# Ex_Controller_ExPwr.net
KiCad netlist of a schematic drawn in EAGLE
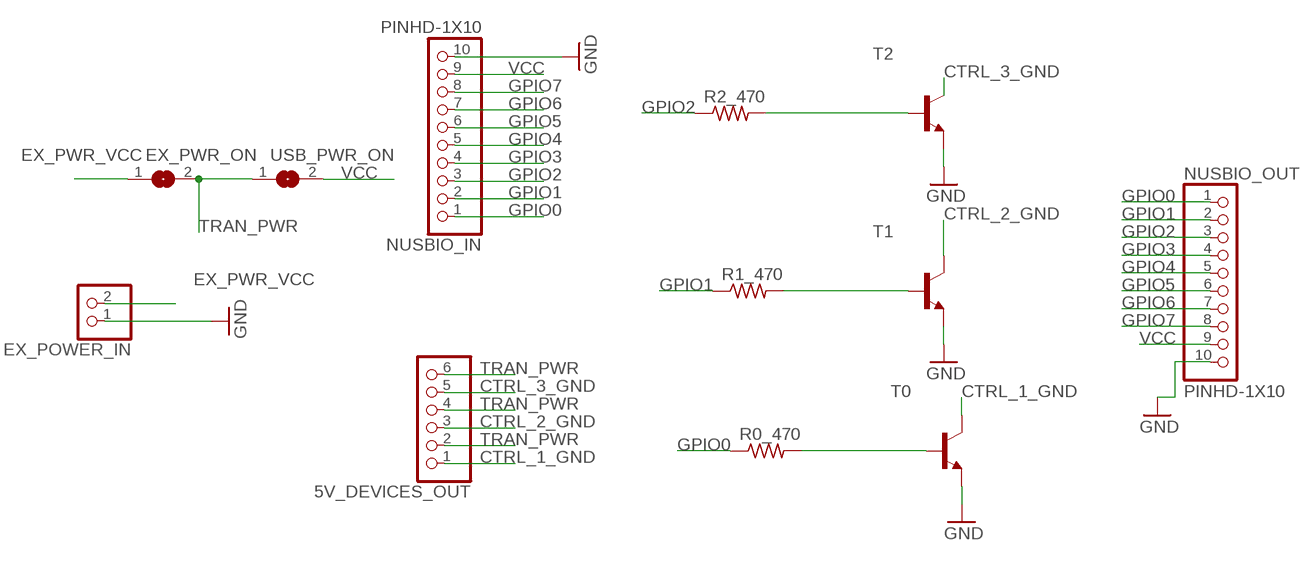
[diagram p0: schematic, sheet 1]

(export (version "E")
  (design (tool "Eeschema 10.0.6"))
  (components
    (comp (ref "5V_DEVICES_OUT")
      (value "PINHD-1X6")
      (footprint "eagle-import:1X06")
      (libsource (lib "eagle-import") (part "PINHD-1X6"))
    )
    (comp (ref "EX_POWER_IN")
      (value "PINHD-1X2")
      (footprint "eagle-import:1X02")
      (libsource (lib "eagle-import") (part "PINHD-1X2"))
    )
    (comp (ref "EX_PWR_ON")
      (value "SOLDERJUMPERREFLOW")
      (footprint "eagle-import:SOLDERJUMPER_REFLOW")
      (libsource (lib "eagle-import") (part "SOLDERJUMPERREFLOW"))
    )
    (comp (ref "NUSBIO_IN")
      (value "PINHD-1X10")
      (footprint "eagle-import:1X10-BIG")
      (libsource (lib "eagle-import") (part "PINHD-1X10"))
    )
    (comp (ref "NUSBIO_OUT")
      (value "PINHD-1X10")
      (footprint "eagle-import:1X10-BIG")
      (libsource (lib "eagle-import") (part "PINHD-1X10"))
    )
    (comp (ref "R0_470")
      (value "R-US_R0805")
      (footprint "eagle-import:R0805")
      (libsource (lib "eagle-import") (part "R-US_R0805"))
    )
    (comp (ref "R1_470")
      (value "R-US_R0805")
      (footprint "eagle-import:R0805")
      (libsource (lib "eagle-import") (part "R-US_R0805"))
    )
    (comp (ref "R2_470")
      (value "R-US_R0805")
      (footprint "eagle-import:R0805")
      (libsource (lib "eagle-import") (part "R-US_R0805"))
    )
    (comp (ref "T0")
      (value "MMBT3904LT1-NPN-SOT23-BEC")
      (footprint "eagle-import:SOT23-BEC")
      (libsource (lib "eagle-import") (part "-NPN-SOT23-BECMMBT3904LT1"))
    )
    (comp (ref "T1")
      (value "MMBT3904LT1-NPN-SOT23-BEC")
      (footprint "eagle-import:SOT23-BEC")
      (libsource (lib "eagle-import") (part "-NPN-SOT23-BECMMBT3904LT1"))
    )
    (comp (ref "T2")
      (value "MMBT3904LT1-NPN-SOT23-BEC")
      (footprint "eagle-import:SOT23-BEC")
      (libsource (lib "eagle-import") (part "-NPN-SOT23-BECMMBT3904LT1"))
    )
    (comp (ref "USB_PWR_ON")
      (value "SOLDERJUMPERREFLOW")
      (footprint "eagle-import:SOLDERJUMPER_REFLOW")
      (libsource (lib "eagle-import") (part "SOLDERJUMPERREFLOW"))
    )
  )
  (nets
    (net (code "1") (name "/CTRL_1_GND") (class "Default")
      (node (ref "5V_DEVICES_OUT") (pin "1") (pinfunction "1_1") (pintype "passive"))
      (node (ref "T0") (pin "C") (pinfunction "C_C") (pintype "passive"))
    )
    (net (code "2") (name "/CTRL_2_GND") (class "Default")
      (node (ref "5V_DEVICES_OUT") (pin "3") (pinfunction "3_3") (pintype "passive"))
      (node (ref "T1") (pin "C") (pinfunction "C_C") (pintype "passive"))
    )
    (net (code "3") (name "/CTRL_3_GND") (class "Default")
      (node (ref "5V_DEVICES_OUT") (pin "5") (pinfunction "5_5") (pintype "passive"))
      (node (ref "T2") (pin "C") (pinfunction "C_C") (pintype "passive"))
    )
    (net (code "4") (name "/EX_PWR_VCC") (class "Default")
      (node (ref "EX_POWER_IN") (pin "2") (pinfunction "2_2") (pintype "passive"))
      (node (ref "EX_PWR_ON") (pin "1") (pinfunction "1_1") (pintype "passive"))
    )
    (net (code "5") (name "/GPIO0") (class "Default")
      (node (ref "NUSBIO_IN") (pin "1") (pinfunction "1_1") (pintype "passive"))
      (node (ref "NUSBIO_OUT") (pin "1") (pinfunction "1_1") (pintype "passive"))
      (node (ref "R0_470") (pin "1") (pinfunction "1_1") (pintype "passive"))
    )
    (net (code "6") (name "/GPIO1") (class "Default")
      (node (ref "NUSBIO_IN") (pin "2") (pinfunction "2_2") (pintype "passive"))
      (node (ref "NUSBIO_OUT") (pin "2") (pinfunction "2_2") (pintype "passive"))
      (node (ref "R1_470") (pin "1") (pinfunction "1_1") (pintype "passive"))
    )
    (net (code "7") (name "/GPIO2") (class "Default")
      (node (ref "NUSBIO_IN") (pin "3") (pinfunction "3_3") (pintype "passive"))
      (node (ref "NUSBIO_OUT") (pin "3") (pinfunction "3_3") (pintype "passive"))
      (node (ref "R2_470") (pin "1") (pinfunction "1_1") (pintype "passive"))
    )
    (net (code "8") (name "/GPIO3") (class "Default")
      (node (ref "NUSBIO_IN") (pin "4") (pinfunction "4_4") (pintype "passive"))
      (node (ref "NUSBIO_OUT") (pin "4") (pinfunction "4_4") (pintype "passive"))
    )
    (net (code "9") (name "/GPIO4") (class "Default")
      (node (ref "NUSBIO_IN") (pin "5") (pinfunction "5_5") (pintype "passive"))
      (node (ref "NUSBIO_OUT") (pin "5") (pinfunction "5_5") (pintype "passive"))
    )
    (net (code "10") (name "/GPIO5") (class "Default")
      (node (ref "NUSBIO_IN") (pin "6") (pinfunction "6_6") (pintype "passive"))
      (node (ref "NUSBIO_OUT") (pin "6") (pinfunction "6_6") (pintype "passive"))
    )
    (net (code "11") (name "/GPIO6") (class "Default")
      (node (ref "NUSBIO_IN") (pin "7") (pinfunction "7_7") (pintype "passive"))
      (node (ref "NUSBIO_OUT") (pin "7") (pinfunction "7_7") (pintype "passive"))
    )
    (net (code "12") (name "/GPIO7") (class "Default")
      (node (ref "NUSBIO_IN") (pin "8") (pinfunction "8_8") (pintype "passive"))
      (node (ref "NUSBIO_OUT") (pin "8") (pinfunction "8_8") (pintype "passive"))
    )
    (net (code "13") (name "/TRAN_PWR") (class "Default")
      (node (ref "5V_DEVICES_OUT") (pin "2") (pinfunction "2_2") (pintype "passive"))
      (node (ref "5V_DEVICES_OUT") (pin "4") (pinfunction "4_4") (pintype "passive"))
      (node (ref "5V_DEVICES_OUT") (pin "6") (pinfunction "6_6") (pintype "passive"))
      (node (ref "EX_PWR_ON") (pin "2") (pinfunction "2_2") (pintype "passive"))
      (node (ref "USB_PWR_ON") (pin "1") (pinfunction "1_1") (pintype "passive"))
    )
    (net (code "14") (name "/VCC") (class "Default")
      (node (ref "NUSBIO_IN") (pin "9") (pinfunction "9_9") (pintype "passive"))
      (node (ref "NUSBIO_OUT") (pin "9") (pinfunction "9_9") (pintype "passive"))
      (node (ref "USB_PWR_ON") (pin "2") (pinfunction "2_2") (pintype "passive"))
    )
    (net (code "15") (name "GND") (class "Default")
      (node (ref "EX_POWER_IN") (pin "1") (pinfunction "1_1") (pintype "passive"))
      (node (ref "NUSBIO_IN") (pin "10") (pinfunction "10_10") (pintype "passive"))
      (node (ref "NUSBIO_OUT") (pin "10") (pinfunction "10_10") (pintype "passive"))
      (node (ref "T0") (pin "E") (pinfunction "E_E") (pintype "passive"))
      (node (ref "T1") (pin "E") (pinfunction "E_E") (pintype "passive"))
      (node (ref "T2") (pin "E") (pinfunction "E_E") (pintype "passive"))
    )
    (net (code "16") (name "Net-(R0_470-Pad2)") (class "Default")
      (node (ref "R0_470") (pin "2") (pinfunction "2_2") (pintype "passive"))
      (node (ref "T0") (pin "B") (pinfunction "B_B") (pintype "passive"))
    )
    (net (code "17") (name "Net-(R1_470-Pad2)") (class "Default")
      (node (ref "R1_470") (pin "2") (pinfunction "2_2") (pintype "passive"))
      (node (ref "T1") (pin "B") (pinfunction "B_B") (pintype "passive"))
    )
    (net (code "18") (name "Net-(R2_470-Pad2)") (class "Default")
      (node (ref "R2_470") (pin "2") (pinfunction "2_2") (pintype "passive"))
      (node (ref "T2") (pin "B") (pinfunction "B_B") (pintype "passive"))
    )
  )
)
